# USBHume2.net
KiCad netlist of a schematic drawn in EAGLE
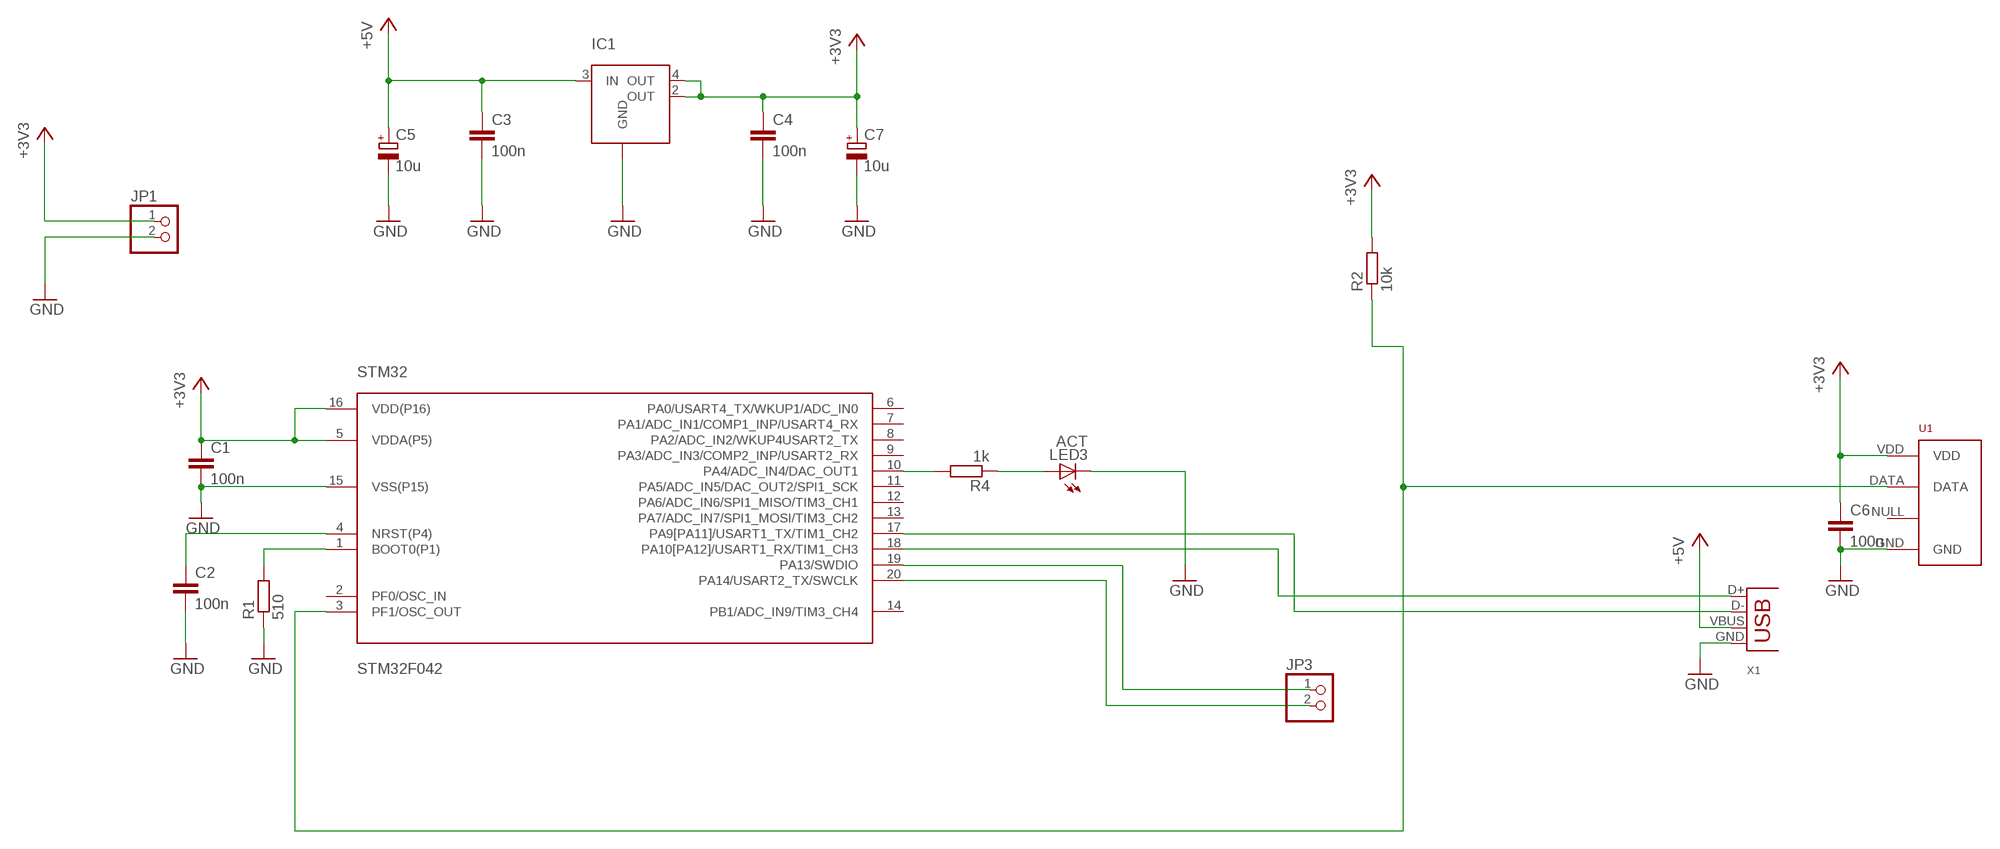
[diagram p0: schematic, sheet 1]

(export (version "E")
  (design (tool "Eeschema 10.0.6"))
  (components
    (comp (ref "C1")
      (value "100n")
      (footprint "eagle-import:C1206K")
      (libsource (lib "eagle-import") (part "C-EUC1206K"))
    )
    (comp (ref "C2")
      (value "100n")
      (footprint "eagle-import:C1206K")
      (libsource (lib "eagle-import") (part "C-EUC1206K"))
    )
    (comp (ref "C3")
      (value "100n")
      (footprint "eagle-import:C1206K")
      (libsource (lib "eagle-import") (part "C-EUC1206K"))
    )
    (comp (ref "C4")
      (value "100n")
      (footprint "eagle-import:C1206K")
      (libsource (lib "eagle-import") (part "C-EUC1206K"))
    )
    (comp (ref "C5")
      (value "10u")
      (footprint "eagle-import:C_6032-28R")
      (libsource (lib "eagle-import") (part "CPOL-EUC/6032-28R"))
    )
    (comp (ref "C6")
      (value "100n")
      (footprint "eagle-import:C1206K")
      (libsource (lib "eagle-import") (part "C-EUC1206K"))
    )
    (comp (ref "C7")
      (value "10u")
      (footprint "eagle-import:C_6032-28R")
      (libsource (lib "eagle-import") (part "CPOL-EUC/6032-28R"))
    )
    (comp (ref "IC1")
      (value "LM1117MP-3.3")
      (footprint "eagle-import:SOT223")
      (libsource (lib "eagle-import") (part "LM1117MP-3.3"))
    )
    (comp (ref "JP1")
      (value "PINHD-1X2")
      (footprint "eagle-import:1X02")
      (libsource (lib "eagle-import") (part "PINHD-1X2"))
    )
    (comp (ref "JP3")
      (value "PINHD-1X2")
      (footprint "eagle-import:1X02")
      (libsource (lib "eagle-import") (part "PINHD-1X2"))
    )
    (comp (ref "LED3")
      (value "ACT")
      (footprint "eagle-import:CHIPLED_0805")
      (libsource (lib "eagle-import") (part "LEDCHIPLED_0805"))
    )
    (comp (ref "R1")
      (value "510")
      (footprint "eagle-import:M0805")
      (libsource (lib "eagle-import") (part "R-EU_M0805"))
    )
    (comp (ref "R2")
      (value "10k")
      (footprint "eagle-import:M0805")
      (libsource (lib "eagle-import") (part "R-EU_M0805"))
    )
    (comp (ref "R4")
      (value "1k")
      (footprint "eagle-import:M0805")
      (libsource (lib "eagle-import") (part "R-EU_M0805"))
    )
    (comp (ref "STM32")
      (value "STM32F042")
      (footprint "eagle-import:TSSOP20")
      (libsource (lib "eagle-import") (part "STM32F042"))
    )
    (comp (ref "U1")
      (value "RHT03_DHT-22_AM2302WIRED")
      (footprint "eagle-import:AM2302")
      (libsource (lib "eagle-import") (part "RHT03_DHT-22_AM2302WIRED"))
    )
    (comp (ref "X1")
      (value "USB-A-H")
      (footprint "eagle-import:USB-A-H")
      (libsource (lib "eagle-import") (part "USB-A-H"))
    )
  )
  (nets
    (net (code "1") (name "+3V3") (class "Default")
      (node (ref "C1") (pin "1") (pinfunction "1_1") (pintype "passive"))
      (node (ref "C4") (pin "1") (pinfunction "1_1") (pintype "passive"))
      (node (ref "C6") (pin "1") (pinfunction "1_1") (pintype "passive"))
      (node (ref "C7") (pin "+") (pinfunction "+_+") (pintype "passive"))
      (node (ref "IC1") (pin "2") (pinfunction "OUT_2") (pintype "power_in"))
      (node (ref "IC1") (pin "4") (pinfunction "OUT_4") (pintype "power_in"))
      (node (ref "JP1") (pin "1") (pinfunction "1_1") (pintype "passive"))
      (node (ref "R2") (pin "2") (pinfunction "2_2") (pintype "passive"))
      (node (ref "STM32") (pin "16") (pinfunction "VDD(P16)_16") (pintype "bidirectional"))
      (node (ref "STM32") (pin "5") (pinfunction "VDDA(P5)_5") (pintype "bidirectional"))
      (node (ref "U1") (pin "VDD") (pinfunction "VDD_VDD") (pintype "power_in"))
    )
    (net (code "2") (name "+5V") (class "Default")
      (node (ref "C3") (pin "1") (pinfunction "1_1") (pintype "passive"))
      (node (ref "C5") (pin "+") (pinfunction "+_+") (pintype "passive"))
      (node (ref "IC1") (pin "3") (pinfunction "IN_3") (pintype "power_in"))
      (node (ref "X1") (pin "VBUS") (pinfunction "VBUS_VBUS") (pintype "bidirectional"))
    )
    (net (code "3") (name "GND") (class "Default")
      (node (ref "C1") (pin "2") (pinfunction "2_2") (pintype "passive"))
      (node (ref "C2") (pin "2") (pinfunction "2_2") (pintype "passive"))
      (node (ref "C3") (pin "2") (pinfunction "2_2") (pintype "passive"))
      (node (ref "C4") (pin "2") (pinfunction "2_2") (pintype "passive"))
      (node (ref "C5") (pin "-") (pinfunction "-_-") (pintype "passive"))
      (node (ref "C6") (pin "2") (pinfunction "2_2") (pintype "passive"))
      (node (ref "C7") (pin "-") (pinfunction "-_-") (pintype "passive"))
      (node (ref "IC1") (pin "1") (pinfunction "GND_1") (pintype "power_in"))
      (node (ref "JP1") (pin "2") (pinfunction "2_2") (pintype "passive"))
      (node (ref "LED3") (pin "C") (pinfunction "C_C") (pintype "passive"))
      (node (ref "R1") (pin "1") (pinfunction "1_1") (pintype "passive"))
      (node (ref "STM32") (pin "15") (pinfunction "VSS(P15)_15") (pintype "bidirectional"))
      (node (ref "U1") (pin "GND") (pinfunction "GND_GND") (pintype "power_in"))
      (node (ref "X1") (pin "GND") (pinfunction "GND_GND") (pintype "bidirectional"))
    )
    (net (code "4") (name "Net-(LED3-PadA)") (class "Default")
      (node (ref "LED3") (pin "A") (pinfunction "A_A") (pintype "passive"))
      (node (ref "R4") (pin "1") (pinfunction "1_1") (pintype "passive"))
    )
    (net (code "5") (name "Net-(STM32-BOOT0(P1))") (class "Default")
      (node (ref "R1") (pin "2") (pinfunction "2_2") (pintype "passive"))
      (node (ref "STM32") (pin "1") (pinfunction "BOOT0(P1)_1") (pintype "bidirectional"))
    )
    (net (code "6") (name "Net-(STM32-NRST(P4))") (class "Default")
      (node (ref "C2") (pin "1") (pinfunction "1_1") (pintype "passive"))
      (node (ref "STM32") (pin "4") (pinfunction "NRST(P4)_4") (pintype "bidirectional"))
    )
    (net (code "7") (name "Net-(STM32-PA4{slash}ADC_IN4{slash}DAC_OUT1)") (class "Default")
      (node (ref "R4") (pin "2") (pinfunction "2_2") (pintype "passive"))
      (node (ref "STM32") (pin "10") (pinfunction "PA4/ADC_IN4/DAC_OUT1_10") (pintype "bidirectional"))
    )
    (net (code "8") (name "Net-(STM32-PA9[PA11]{slash}USART1_TX{slash}TIM1_CH2)") (class "Default")
      (node (ref "STM32") (pin "17") (pinfunction "PA9[PA11]/USART1_TX/TIM1_CH2_17") (pintype "bidirectional"))
      (node (ref "X1") (pin "D-") (pinfunction "D-_D-") (pintype "bidirectional"))
    )
    (net (code "9") (name "Net-(STM32-PA10[PA12]{slash}USART1_RX{slash}TIM1_CH3)") (class "Default")
      (node (ref "STM32") (pin "18") (pinfunction "PA10[PA12]/USART1_RX/TIM1_CH3_18") (pintype "bidirectional"))
      (node (ref "X1") (pin "D+") (pinfunction "D+_D+") (pintype "bidirectional"))
    )
    (net (code "10") (name "Net-(STM32-PA13{slash}SWDIO)") (class "Default")
      (node (ref "JP3") (pin "1") (pinfunction "1_1") (pintype "passive"))
      (node (ref "STM32") (pin "19") (pinfunction "PA13/SWDIO_19") (pintype "bidirectional"))
    )
    (net (code "11") (name "Net-(STM32-PA14{slash}USART2_TX{slash}SWCLK)") (class "Default")
      (node (ref "JP3") (pin "2") (pinfunction "2_2") (pintype "passive"))
      (node (ref "STM32") (pin "20") (pinfunction "PA14/USART2_TX/SWCLK_20") (pintype "bidirectional"))
    )
    (net (code "12") (name "Net-(STM32-PF1{slash}OSC_OUT)") (class "Default")
      (node (ref "R2") (pin "1") (pinfunction "1_1") (pintype "passive"))
      (node (ref "STM32") (pin "3") (pinfunction "PF1/OSC_OUT_3") (pintype "bidirectional"))
      (node (ref "U1") (pin "DATA") (pinfunction "DATA_DATA") (pintype "bidirectional"))
    )
    (net (code "13") (name "unconnected-(STM32-PA0{slash}USART4_TX{slash}WKUP1{slash}ADC_IN0-Pad6)") (class "Default")
      (node (ref "STM32") (pin "6") (pinfunction "PA0/USART4_TX/WKUP1/ADC_IN0_6") (pintype "bidirectional"))
    )
    (net (code "14") (name "unconnected-(STM32-PA1{slash}ADC_IN1{slash}COMP1_INP{slash}USART4_RX-Pad7)") (class "Default")
      (node (ref "STM32") (pin "7") (pinfunction "PA1/ADC_IN1/COMP1_INP/USART4_RX_7") (pintype "bidirectional"))
    )
    (net (code "15") (name "unconnected-(STM32-PA2{slash}ADC_IN2{slash}WKUP4USART2_TX-Pad8)") (class "Default")
      (node (ref "STM32") (pin "8") (pinfunction "PA2/ADC_IN2/WKUP4USART2_TX_8") (pintype "bidirectional"))
    )
    (net (code "16") (name "unconnected-(STM32-PA3{slash}ADC_IN3{slash}COMP2_INP{slash}USART2_RX-Pad9)") (class "Default")
      (node (ref "STM32") (pin "9") (pinfunction "PA3/ADC_IN3/COMP2_INP/USART2_RX_9") (pintype "bidirectional"))
    )
    (net (code "17") (name "unconnected-(STM32-PA5{slash}ADC_IN5{slash}DAC_OUT2{slash}SPI1_SCK-Pad11)") (class "Default")
      (node (ref "STM32") (pin "11") (pinfunction "PA5/ADC_IN5/DAC_OUT2/SPI1_SCK_11") (pintype "bidirectional"))
    )
    (net (code "18") (name "unconnected-(STM32-PA6{slash}ADC_IN6{slash}SPI1_MISO{slash}TIM3_CH1-Pad12)") (class "Default")
      (node (ref "STM32") (pin "12") (pinfunction "PA6/ADC_IN6/SPI1_MISO/TIM3_CH1_12") (pintype "bidirectional"))
    )
    (net (code "19") (name "unconnected-(STM32-PA7{slash}ADC_IN7{slash}SPI1_MOSI{slash}TIM3_CH2-Pad13)") (class "Default")
      (node (ref "STM32") (pin "13") (pinfunction "PA7/ADC_IN7/SPI1_MOSI/TIM3_CH2_13") (pintype "bidirectional"))
    )
    (net (code "20") (name "unconnected-(STM32-PB1{slash}ADC_IN9{slash}TIM3_CH4-Pad14)") (class "Default")
      (node (ref "STM32") (pin "14") (pinfunction "PB1/ADC_IN9/TIM3_CH4_14") (pintype "bidirectional"))
    )
    (net (code "21") (name "unconnected-(STM32-PF0{slash}OSC_IN-Pad2)") (class "Default")
      (node (ref "STM32") (pin "2") (pinfunction "PF0/OSC_IN_2") (pintype "bidirectional"))
    )
    (net (code "22") (name "unconnected-(U1-PadNULL)") (class "Default")
      (node (ref "U1") (pin "NULL") (pinfunction "NULL_NULL") (pintype "no_connect"))
    )
  )
)
